# MotorDriver.net
KiCad netlist of a schematic drawn in Altium Designer
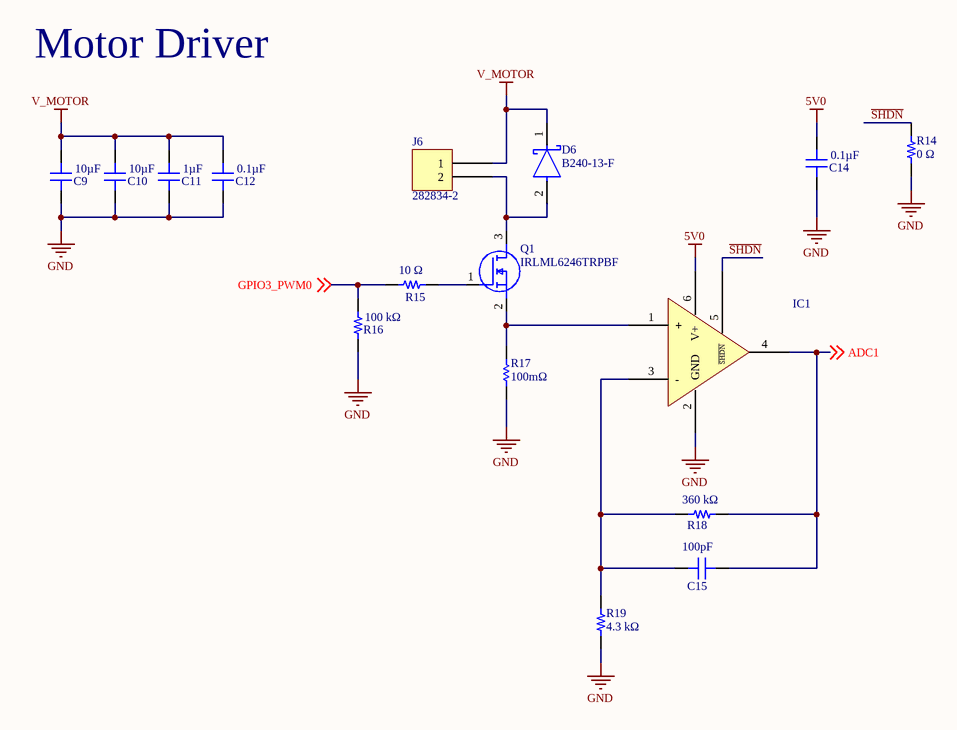
[diagram p0: MotorDriver.SchDoc]

(export (version "E")
  (design (tool "Eeschema 10.0.6"))
  (components
    (comp (ref "C9")
      (value "10µF")
      (footprint "CAP 0805_2012")
      (description "CAP CER 10UF 25V X5R 0805")
      (fields (field (name "PART NUMBER") "08053D106KAT2A") (field (name "MANUFACTURER") "AVX Corporation"))
      (libsource (lib "Generic Altium Database") (part "Capacitor"))
    )
    (comp (ref "C10")
      (value "10µF")
      (footprint "CAP 0805_2012")
      (description "CAP CER 10UF 25V X5R 0805")
      (fields (field (name "PART NUMBER") "08053D106KAT2A") (field (name "MANUFACTURER") "AVX Corporation"))
      (libsource (lib "Generic Altium Database") (part "Capacitor"))
    )
    (comp (ref "C11")
      (value "1µF")
      (footprint "CAP 0805_2012")
      (description "CAP CER 1UF 25V X7R 0805")
      (fields (field (name "PART NUMBER") "08053C105JAT2A") (field (name "MANUFACTURER") "AVX Corporation"))
      (libsource (lib "Generic Altium Database") (part "Capacitor"))
    )
    (comp (ref "C12")
      (value "0.1µF")
      (footprint "CAP 0603_1608")
      (description "CAP CER 0.1UF 25V X7R 0603")
      (fields (field (name "PART NUMBER") "06033C104JAT2A") (field (name "MANUFACTURER") "AVX Corporation"))
      (libsource (lib "Generic Altium Database") (part "Capacitor"))
    )
    (comp (ref "C14")
      (value "0.1µF")
      (footprint "CAP 0603_1608")
      (description "CAP CER 0.1UF 25V X7R 0603")
      (fields (field (name "PART NUMBER") "06033C104JAT2A") (field (name "MANUFACTURER") "AVX Corporation"))
      (libsource (lib "Generic Altium Database") (part "Capacitor"))
    )
    (comp (ref "C15")
      (value "100pF")
      (footprint "CAP 0603_1608")
      (description "CAP CER 100PF 25V C0G/NP0 0603")
      (fields (field (name "PART NUMBER") "06033A101KAT2A") (field (name "MANUFACTURER") "AVX Corporation"))
      (libsource (lib "Generic Altium Database") (part "Capacitor"))
    )
    (comp (ref "D6")
      (value "B240-13-F")
      (footprint "FP-SMB-MFG")
      (description "DIODE SCHOTTKY 40V 2A SMB")
      (fields
        (field (name "MANUFACTURER") "Diodes Inc.")
        (field (name "OCTOPART") "https://octopart.com/b240-13-f-diodes+inc.-325780")
      )
      (libsource (lib "Altium Content Vault") (part "1d6ec82d83fb6aee721767c19dac4b9"))
    )
    (comp (ref "IC1")
      (value "LMV601MG/NOPB")
      (footprint "TI SC70-6 DCK")
      (description "IC OPAMP GP 1 CIRCUIT SC70-6")
      (fields (field (name "MANUFACTURER") "Texas Instruments"))
      (libsource (lib "Generic Altium Database") (part "TI LMV601"))
    )
    (comp (ref "J6")
      (value "282834-2")
      (footprint "TE 282834-2")
      (description "TERM BLK 2P SIDE ENT 2.54MM PCB")
      (fields (field (name "MANUFACTURER") "TE Connectivity AMP Connectors") (field (name "VOLTAGE") "150V"))
      (libsource (lib "Generic Altium Database") (part "2 Pin"))
    )
    (comp (ref "Q1")
      (value "IRLML6246TRPBF")
      (footprint "SamacSys:SOT95P237X112-3N")
      (description "MOSFET (N-Channel)")
      (fields (field (name "MOUSER PART NUMBER") "942-IRLML6246TRPBF"))
      (libsource (lib "*") (part "IRLML6246TRPBF"))
    )
    (comp (ref "R14")
      (value "0 Ω")
      (footprint "RES 0603_1608")
      (description "RES SMD 0 OHM JUMPER 1/10W 0603")
      (fields (field (name "PART NUMBER") "AC0603FR-070RL") (field (name "MANUFACTURER") "Yageo"))
      (libsource (lib "Generic Altium Database") (part "Resistor"))
    )
    (comp (ref "R15")
      (value "10 Ω")
      (footprint "RES 0603_1608")
      (description "RES SMD 10 OHM 1% 1/10W 0603")
      (fields (field (name "PART NUMBER") "AC0603FR-0710RL") (field (name "MANUFACTURER") "Yageo"))
      (libsource (lib "Generic Altium Database") (part "Resistor"))
    )
    (comp (ref "R16")
      (value "100 kΩ")
      (footprint "RES 0603_1608")
      (description "RES SMD 100K OHM 1% 1/10W 0603")
      (fields (field (name "PART NUMBER") "AC0603FR-07100KL") (field (name "MANUFACTURER") "Yageo"))
      (libsource (lib "Generic Altium Database") (part "Resistor"))
    )
    (comp (ref "R17")
      (value "100mΩ")
      (footprint "RESC3216X70X50LL05T20")
      (description "ERJ-L08KF10CV")
      (fields (field (name "MANUFACTURER") "Panasonic"))
      (libsource (lib "Altium Content Vault") (part "RES"))
    )
    (comp (ref "R18")
      (value "360 kΩ")
      (footprint "RES 0603_1608")
      (description "RES SMD 360K OHM 1% 1/10W 0603")
      (fields (field (name "PART NUMBER") "CR0603-FX-3603ELF") (field (name "MANUFACTURER") "Bourns Inc."))
      (libsource (lib "Generic Altium Database") (part "Resistor"))
    )
    (comp (ref "R19")
      (value "4.3 kΩ")
      (footprint "RES 0603_1608")
      (description "RES SMD 4.3K OHM 0.1% 1/16W 0603")
      (fields
        (field (name "PART NUMBER") "CPF0603B4K3E1")
        (field (name "MANUFACTURER") "TE Connectivity Passive Product")
      )
      (libsource (lib "Generic Altium Database") (part "Resistor"))
    )
  )
  (nets
    (net (code "1") (name "/~{SHDN}") (class "Default")
      (node (ref "IC1") (pin "5") (pinfunction "~{SHDN}_5") (pintype "passive"))
      (node (ref "R14") (pin "1") (pinfunction "1_1") (pintype "passive"))
    )
    (net (code "2") (name "5V0") (class "Default")
      (node (ref "C14") (pin "2") (pinfunction "2_2") (pintype "passive"))
      (node (ref "IC1") (pin "6") (pinfunction "V+_6") (pintype "power_in"))
    )
    (net (code "3") (name "ADC1") (class "Default")
      (node (ref "C15") (pin "2") (pinfunction "2_2") (pintype "passive"))
      (node (ref "IC1") (pin "4") (pinfunction "OUT_4") (pintype "passive"))
      (node (ref "R18") (pin "2") (pinfunction "2_2") (pintype "passive"))
    )
    (net (code "4") (name "GND") (class "Default")
      (node (ref "C10") (pin "1") (pinfunction "1_1") (pintype "passive"))
      (node (ref "C11") (pin "1") (pinfunction "1_1") (pintype "passive"))
      (node (ref "C12") (pin "1") (pinfunction "1_1") (pintype "passive"))
      (node (ref "C14") (pin "1") (pinfunction "1_1") (pintype "passive"))
      (node (ref "C9") (pin "1") (pinfunction "1_1") (pintype "passive"))
      (node (ref "IC1") (pin "2") (pinfunction "GND_2") (pintype "power_in"))
      (node (ref "R14") (pin "2") (pinfunction "2_2") (pintype "passive"))
      (node (ref "R16") (pin "1") (pinfunction "1_1") (pintype "passive"))
      (node (ref "R17") (pin "1") (pinfunction "1_1") (pintype "passive"))
      (node (ref "R19") (pin "2") (pinfunction "2_2") (pintype "passive"))
    )
    (net (code "5") (name "GPIO3_PWM0") (class "Default")
      (node (ref "R15") (pin "1") (pinfunction "1_1") (pintype "passive"))
      (node (ref "R16") (pin "2") (pinfunction "2_2") (pintype "passive"))
    )
    (net (code "6") (name "Net-(D6-A)") (class "Default")
      (node (ref "D6") (pin "2") (pinfunction "A_2") (pintype "passive"))
      (node (ref "J6") (pin "2") (pinfunction "2_2") (pintype "passive"))
      (node (ref "Q1") (pin "3") (pinfunction "D_3") (pintype "passive"))
    )
    (net (code "7") (name "Net-(IC1-+)") (class "Default")
      (node (ref "IC1") (pin "1") (pinfunction "+_1") (pintype "passive"))
      (node (ref "Q1") (pin "2") (pinfunction "S_2") (pintype "passive"))
      (node (ref "R17") (pin "2") (pinfunction "2_2") (pintype "passive"))
    )
    (net (code "8") (name "Net-(IC1--)") (class "Default")
      (node (ref "C15") (pin "1") (pinfunction "1_1") (pintype "passive"))
      (node (ref "IC1") (pin "3") (pinfunction "-_3") (pintype "passive"))
      (node (ref "R18") (pin "1") (pinfunction "1_1") (pintype "passive"))
      (node (ref "R19") (pin "1") (pinfunction "1_1") (pintype "passive"))
    )
    (net (code "9") (name "Net-(Q1-G)") (class "Default")
      (node (ref "Q1") (pin "1") (pinfunction "G_1") (pintype "passive"))
      (node (ref "R15") (pin "2") (pinfunction "2_2") (pintype "passive"))
    )
    (net (code "10") (name "V_MOTOR") (class "Default")
      (node (ref "C10") (pin "2") (pinfunction "2_2") (pintype "passive"))
      (node (ref "C11") (pin "2") (pinfunction "2_2") (pintype "passive"))
      (node (ref "C12") (pin "2") (pinfunction "2_2") (pintype "passive"))
      (node (ref "C9") (pin "2") (pinfunction "2_2") (pintype "passive"))
      (node (ref "D6") (pin "1") (pinfunction "C_1") (pintype "passive"))
      (node (ref "J6") (pin "1") (pinfunction "1_1") (pintype "passive"))
    )
  )
)
